# M106X.net
KiCad netlist of a schematic drawn in EAGLE
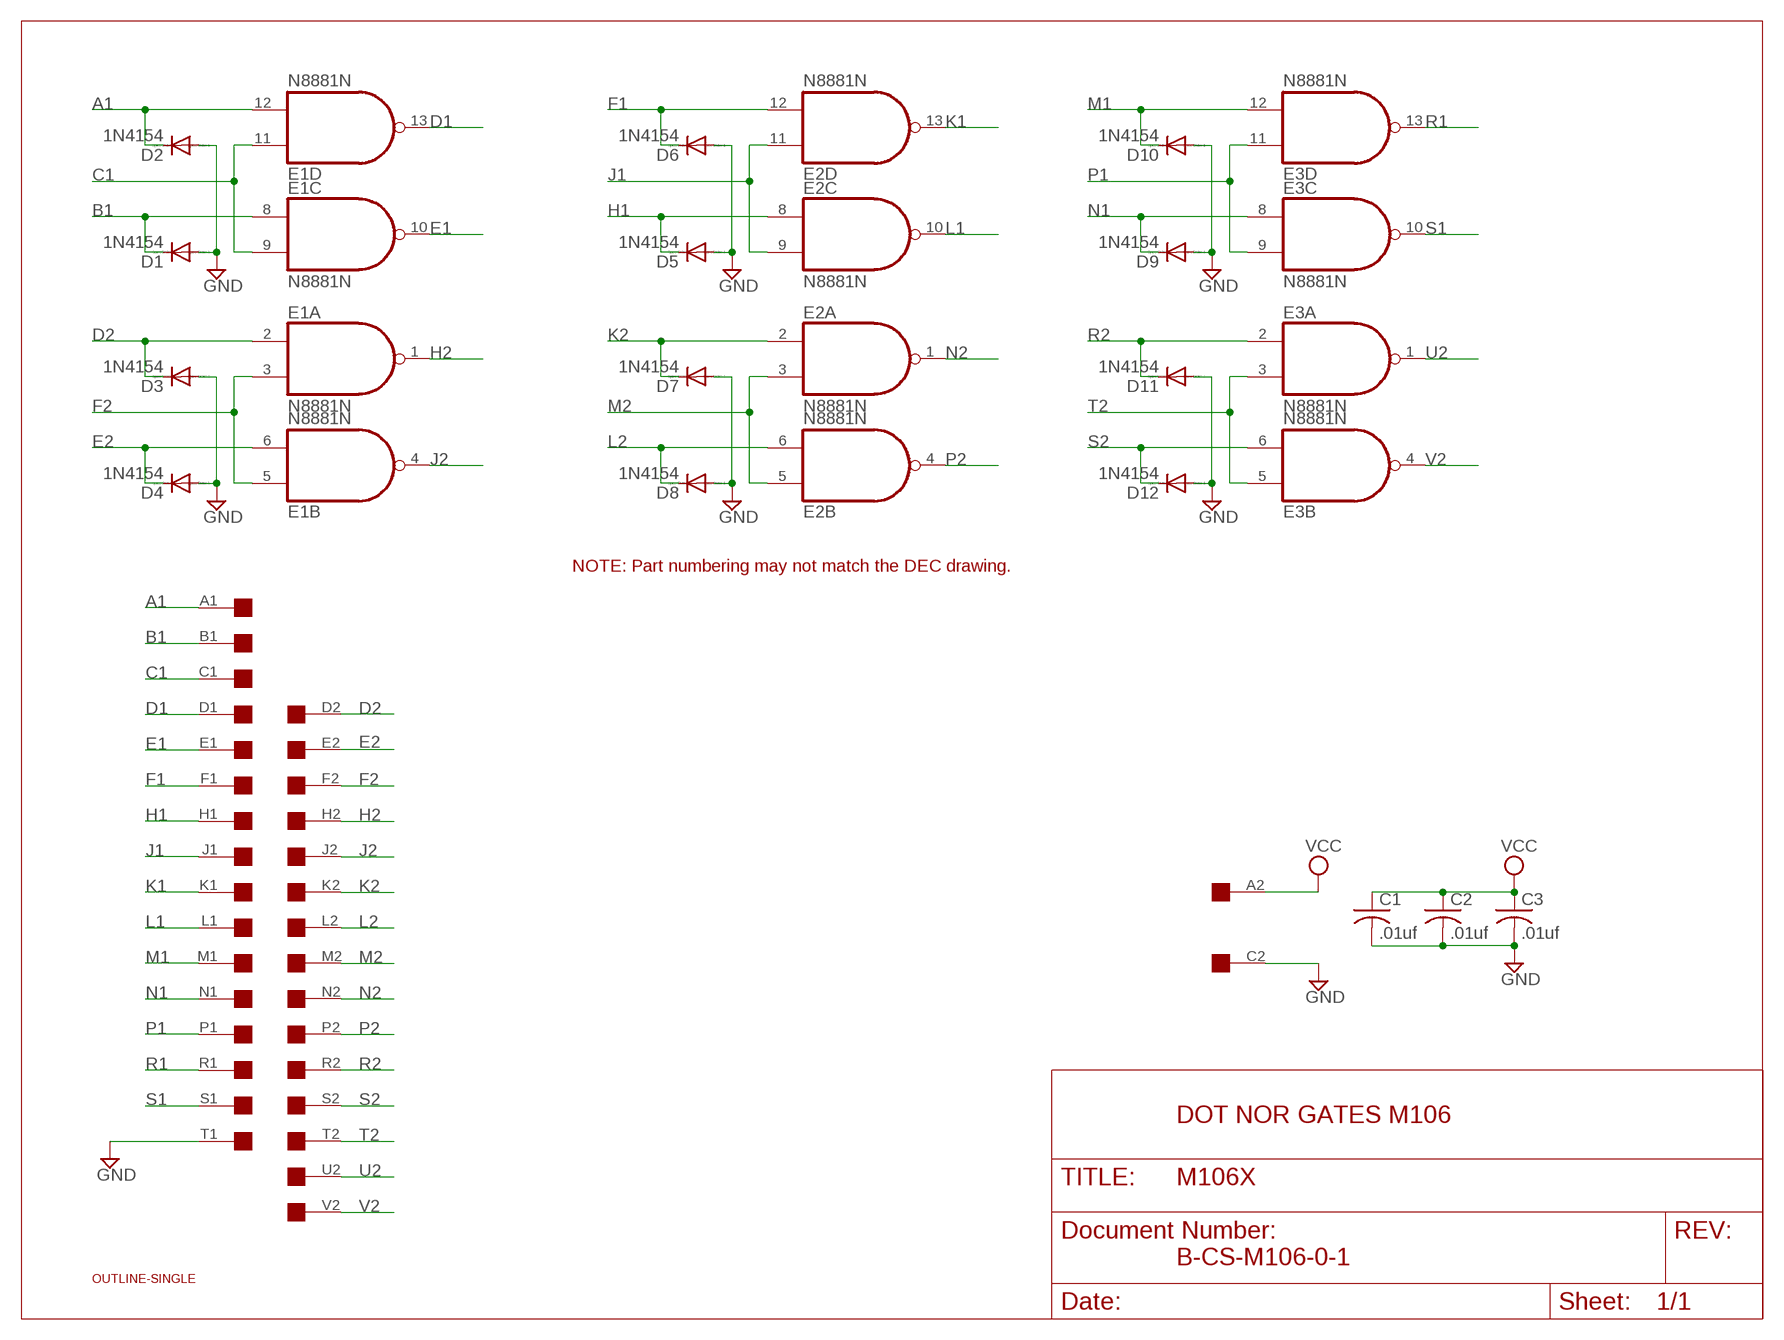
[diagram p0: schematic, sheet 1]

(export (version "E")
  (design (tool "Eeschema 10.0.6"))
  (components
    (comp (ref "C1")
      (value ".01uf")
      (footprint "eagle-import:C050-025X075")
      (libsource (lib "eagle-import") (part "C-US050-025X075"))
    )
    (comp (ref "C2")
      (value ".01uf")
      (footprint "eagle-import:C050-025X075")
      (libsource (lib "eagle-import") (part "C-US050-025X075"))
    )
    (comp (ref "C3")
      (value ".01uf")
      (footprint "eagle-import:C050-025X075")
      (libsource (lib "eagle-import") (part "C-US050-025X075"))
    )
    (comp (ref "D1")
      (value "1N4154")
      (footprint "eagle-import:DO35-10")
      (libsource (lib "eagle-import") (part "1N4148DO35-10"))
    )
    (comp (ref "D2")
      (value "1N4154")
      (footprint "eagle-import:DO35-10")
      (libsource (lib "eagle-import") (part "1N4148DO35-10"))
    )
    (comp (ref "D3")
      (value "1N4154")
      (footprint "eagle-import:DO35-10")
      (libsource (lib "eagle-import") (part "1N4148DO35-10"))
    )
    (comp (ref "D4")
      (value "1N4154")
      (footprint "eagle-import:DO35-10")
      (libsource (lib "eagle-import") (part "1N4148DO35-10"))
    )
    (comp (ref "D5")
      (value "1N4154")
      (footprint "eagle-import:DO35-10")
      (libsource (lib "eagle-import") (part "1N4148DO35-10"))
    )
    (comp (ref "D6")
      (value "1N4154")
      (footprint "eagle-import:DO35-10")
      (libsource (lib "eagle-import") (part "1N4148DO35-10"))
    )
    (comp (ref "D7")
      (value "1N4154")
      (footprint "eagle-import:DO35-10")
      (libsource (lib "eagle-import") (part "1N4148DO35-10"))
    )
    (comp (ref "D8")
      (value "1N4154")
      (footprint "eagle-import:DO35-10")
      (libsource (lib "eagle-import") (part "1N4148DO35-10"))
    )
    (comp (ref "D9")
      (value "1N4154")
      (footprint "eagle-import:DO35-10")
      (libsource (lib "eagle-import") (part "1N4148DO35-10"))
    )
    (comp (ref "D10")
      (value "1N4154")
      (footprint "eagle-import:DO35-10")
      (libsource (lib "eagle-import") (part "1N4148DO35-10"))
    )
    (comp (ref "D11")
      (value "1N4154")
      (footprint "eagle-import:DO35-10")
      (libsource (lib "eagle-import") (part "1N4148DO35-10"))
    )
    (comp (ref "D12")
      (value "1N4154")
      (footprint "eagle-import:DO35-10")
      (libsource (lib "eagle-import") (part "1N4148DO35-10"))
    )
    (comp (ref "E1")
      (value "N8881N")
      (footprint "eagle-import:DIL14")
      (libsource (lib "eagle-import") (part "N8881N"))
    )
    (comp (ref "E2")
      (value "N8881N")
      (footprint "eagle-import:DIL14")
      (libsource (lib "eagle-import") (part "N8881N"))
    )
    (comp (ref "E3")
      (value "N8881N")
      (footprint "eagle-import:DIL14")
      (libsource (lib "eagle-import") (part "N8881N"))
    )
    (comp (ref "U$1")
      (value "SINGLE")
      (footprint "eagle-import:EDGE-CON2")
      (libsource (lib "eagle-import") (part "SINGLE"))
    )
    (comp (ref "U$4")
      (value "OUTLINE-SINGLE")
      (footprint "eagle-import:SINGLE")
      (libsource (lib "eagle-import") (part "OUTLINE-SINGLE"))
    )
  )
  (nets
    (net (code "1") (name "/A1") (class "Default")
      (node (ref "D2") (pin "C") (pinfunction "C_C") (pintype "passive"))
      (node (ref "E1") (pin "12") (pinfunction "I1_12") (pintype "input"))
      (node (ref "U$1") (pin "A1") (pinfunction "1_A1") (pintype "bidirectional"))
    )
    (net (code "2") (name "/B1") (class "Default")
      (node (ref "D1") (pin "C") (pinfunction "C_C") (pintype "passive"))
      (node (ref "E1") (pin "8") (pinfunction "I0_8") (pintype "input"))
      (node (ref "U$1") (pin "B1") (pinfunction "1_B1") (pintype "bidirectional"))
    )
    (net (code "3") (name "/C1") (class "Default")
      (node (ref "E1") (pin "11") (pinfunction "I0_11") (pintype "input"))
      (node (ref "E1") (pin "9") (pinfunction "I1_9") (pintype "input"))
      (node (ref "U$1") (pin "C1") (pinfunction "1_C1") (pintype "bidirectional"))
    )
    (net (code "4") (name "/D1") (class "Default")
      (node (ref "E1") (pin "13") (pinfunction "O_13") (pintype "open_collector"))
      (node (ref "U$1") (pin "D1") (pinfunction "1_D1") (pintype "bidirectional"))
    )
    (net (code "5") (name "/D2") (class "Default")
      (node (ref "D3") (pin "C") (pinfunction "C_C") (pintype "passive"))
      (node (ref "E1") (pin "2") (pinfunction "I0_2") (pintype "input"))
      (node (ref "U$1") (pin "D2") (pinfunction "1_D2") (pintype "bidirectional"))
    )
    (net (code "6") (name "/E1") (class "Default")
      (node (ref "E1") (pin "10") (pinfunction "O_10") (pintype "open_collector"))
      (node (ref "U$1") (pin "E1") (pinfunction "1_E1") (pintype "bidirectional"))
    )
    (net (code "7") (name "/E2") (class "Default")
      (node (ref "D4") (pin "C") (pinfunction "C_C") (pintype "passive"))
      (node (ref "E1") (pin "6") (pinfunction "I1_6") (pintype "input"))
      (node (ref "U$1") (pin "E2") (pinfunction "1_E2") (pintype "bidirectional"))
    )
    (net (code "8") (name "/F1") (class "Default")
      (node (ref "D6") (pin "C") (pinfunction "C_C") (pintype "passive"))
      (node (ref "E2") (pin "12") (pinfunction "I1_12") (pintype "input"))
      (node (ref "U$1") (pin "F1") (pinfunction "1_F1") (pintype "bidirectional"))
    )
    (net (code "9") (name "/F2") (class "Default")
      (node (ref "E1") (pin "3") (pinfunction "I1_3") (pintype "input"))
      (node (ref "E1") (pin "5") (pinfunction "I0_5") (pintype "input"))
      (node (ref "U$1") (pin "F2") (pinfunction "1_F2") (pintype "bidirectional"))
    )
    (net (code "10") (name "/H1") (class "Default")
      (node (ref "D5") (pin "C") (pinfunction "C_C") (pintype "passive"))
      (node (ref "E2") (pin "8") (pinfunction "I0_8") (pintype "input"))
      (node (ref "U$1") (pin "H1") (pinfunction "1_H1") (pintype "bidirectional"))
    )
    (net (code "11") (name "/H2") (class "Default")
      (node (ref "E1") (pin "1") (pinfunction "O_1") (pintype "open_collector"))
      (node (ref "U$1") (pin "H2") (pinfunction "1_H2") (pintype "bidirectional"))
    )
    (net (code "12") (name "/J1") (class "Default")
      (node (ref "E2") (pin "11") (pinfunction "I0_11") (pintype "input"))
      (node (ref "E2") (pin "9") (pinfunction "I1_9") (pintype "input"))
      (node (ref "U$1") (pin "J1") (pinfunction "1_J1") (pintype "bidirectional"))
    )
    (net (code "13") (name "/J2") (class "Default")
      (node (ref "E1") (pin "4") (pinfunction "O_4") (pintype "open_collector"))
      (node (ref "U$1") (pin "J2") (pinfunction "1_J2") (pintype "bidirectional"))
    )
    (net (code "14") (name "/K1") (class "Default")
      (node (ref "E2") (pin "13") (pinfunction "O_13") (pintype "open_collector"))
      (node (ref "U$1") (pin "K1") (pinfunction "1_K1") (pintype "bidirectional"))
    )
    (net (code "15") (name "/K2") (class "Default")
      (node (ref "D7") (pin "C") (pinfunction "C_C") (pintype "passive"))
      (node (ref "E2") (pin "2") (pinfunction "I0_2") (pintype "input"))
      (node (ref "U$1") (pin "K2") (pinfunction "1_K2") (pintype "bidirectional"))
    )
    (net (code "16") (name "/L1") (class "Default")
      (node (ref "E2") (pin "10") (pinfunction "O_10") (pintype "open_collector"))
      (node (ref "U$1") (pin "L1") (pinfunction "1_L1") (pintype "bidirectional"))
    )
    (net (code "17") (name "/L2") (class "Default")
      (node (ref "D8") (pin "C") (pinfunction "C_C") (pintype "passive"))
      (node (ref "E2") (pin "6") (pinfunction "I1_6") (pintype "input"))
      (node (ref "U$1") (pin "L2") (pinfunction "1_L2") (pintype "bidirectional"))
    )
    (net (code "18") (name "/M1") (class "Default")
      (node (ref "D10") (pin "C") (pinfunction "C_C") (pintype "passive"))
      (node (ref "E3") (pin "12") (pinfunction "I1_12") (pintype "input"))
      (node (ref "U$1") (pin "M1") (pinfunction "1_M1") (pintype "bidirectional"))
    )
    (net (code "19") (name "/M2") (class "Default")
      (node (ref "E2") (pin "3") (pinfunction "I1_3") (pintype "input"))
      (node (ref "E2") (pin "5") (pinfunction "I0_5") (pintype "input"))
      (node (ref "U$1") (pin "M2") (pinfunction "1_M2") (pintype "bidirectional"))
    )
    (net (code "20") (name "/N1") (class "Default")
      (node (ref "D9") (pin "C") (pinfunction "C_C") (pintype "passive"))
      (node (ref "E3") (pin "8") (pinfunction "I0_8") (pintype "input"))
      (node (ref "U$1") (pin "N1") (pinfunction "1_N1") (pintype "bidirectional"))
    )
    (net (code "21") (name "/N2") (class "Default")
      (node (ref "E2") (pin "1") (pinfunction "O_1") (pintype "open_collector"))
      (node (ref "U$1") (pin "N2") (pinfunction "1_N2") (pintype "bidirectional"))
    )
    (net (code "22") (name "/P1") (class "Default")
      (node (ref "E3") (pin "11") (pinfunction "I0_11") (pintype "input"))
      (node (ref "E3") (pin "9") (pinfunction "I1_9") (pintype "input"))
      (node (ref "U$1") (pin "P1") (pinfunction "1_P1") (pintype "bidirectional"))
    )
    (net (code "23") (name "/P2") (class "Default")
      (node (ref "E2") (pin "4") (pinfunction "O_4") (pintype "open_collector"))
      (node (ref "U$1") (pin "P2") (pinfunction "1_P2") (pintype "bidirectional"))
    )
    (net (code "24") (name "/R1") (class "Default")
      (node (ref "E3") (pin "13") (pinfunction "O_13") (pintype "open_collector"))
      (node (ref "U$1") (pin "R1") (pinfunction "1_R1") (pintype "bidirectional"))
    )
    (net (code "25") (name "/R2") (class "Default")
      (node (ref "D11") (pin "C") (pinfunction "C_C") (pintype "passive"))
      (node (ref "E3") (pin "2") (pinfunction "I0_2") (pintype "input"))
      (node (ref "U$1") (pin "R2") (pinfunction "1_R2") (pintype "bidirectional"))
    )
    (net (code "26") (name "/S1") (class "Default")
      (node (ref "E3") (pin "10") (pinfunction "O_10") (pintype "open_collector"))
      (node (ref "U$1") (pin "S1") (pinfunction "1_S1") (pintype "bidirectional"))
    )
    (net (code "27") (name "/S2") (class "Default")
      (node (ref "D12") (pin "C") (pinfunction "C_C") (pintype "passive"))
      (node (ref "E3") (pin "6") (pinfunction "I1_6") (pintype "input"))
      (node (ref "U$1") (pin "S2") (pinfunction "1_S2") (pintype "bidirectional"))
    )
    (net (code "28") (name "/T2") (class "Default")
      (node (ref "E3") (pin "3") (pinfunction "I1_3") (pintype "input"))
      (node (ref "E3") (pin "5") (pinfunction "I0_5") (pintype "input"))
      (node (ref "U$1") (pin "T2") (pinfunction "1_T2") (pintype "bidirectional"))
    )
    (net (code "29") (name "/U2") (class "Default")
      (node (ref "E3") (pin "1") (pinfunction "O_1") (pintype "open_collector"))
      (node (ref "U$1") (pin "U2") (pinfunction "1_U2") (pintype "bidirectional"))
    )
    (net (code "30") (name "/V2") (class "Default")
      (node (ref "E3") (pin "4") (pinfunction "O_4") (pintype "open_collector"))
      (node (ref "U$1") (pin "V2") (pinfunction "1_V2") (pintype "bidirectional"))
    )
    (net (code "31") (name "GND") (class "Default")
      (node (ref "C1") (pin "2") (pinfunction "2_2") (pintype "passive"))
      (node (ref "C2") (pin "2") (pinfunction "2_2") (pintype "passive"))
      (node (ref "C3") (pin "2") (pinfunction "2_2") (pintype "passive"))
      (node (ref "D1") (pin "A") (pinfunction "A_A") (pintype "passive"))
      (node (ref "D10") (pin "A") (pinfunction "A_A") (pintype "passive"))
      (node (ref "D11") (pin "A") (pinfunction "A_A") (pintype "passive"))
      (node (ref "D12") (pin "A") (pinfunction "A_A") (pintype "passive"))
      (node (ref "D2") (pin "A") (pinfunction "A_A") (pintype "passive"))
      (node (ref "D3") (pin "A") (pinfunction "A_A") (pintype "passive"))
      (node (ref "D4") (pin "A") (pinfunction "A_A") (pintype "passive"))
      (node (ref "D5") (pin "A") (pinfunction "A_A") (pintype "passive"))
      (node (ref "D6") (pin "A") (pinfunction "A_A") (pintype "passive"))
      (node (ref "D7") (pin "A") (pinfunction "A_A") (pintype "passive"))
      (node (ref "D8") (pin "A") (pinfunction "A_A") (pintype "passive"))
      (node (ref "D9") (pin "A") (pinfunction "A_A") (pintype "passive"))
      (node (ref "U$1") (pin "C2") (pinfunction "1_C2") (pintype "bidirectional"))
      (node (ref "U$1") (pin "T1") (pinfunction "1_T1") (pintype "bidirectional"))
    )
    (net (code "32") (name "VCC") (class "Default")
      (node (ref "C1") (pin "1") (pinfunction "1_1") (pintype "passive"))
      (node (ref "C2") (pin "1") (pinfunction "1_1") (pintype "passive"))
      (node (ref "C3") (pin "1") (pinfunction "1_1") (pintype "passive"))
      (node (ref "U$1") (pin "A2") (pinfunction "1_A2") (pintype "bidirectional"))
    )
  )
)
